# pokey.net
KiCad netlist of a schematic drawn in Altium Designer
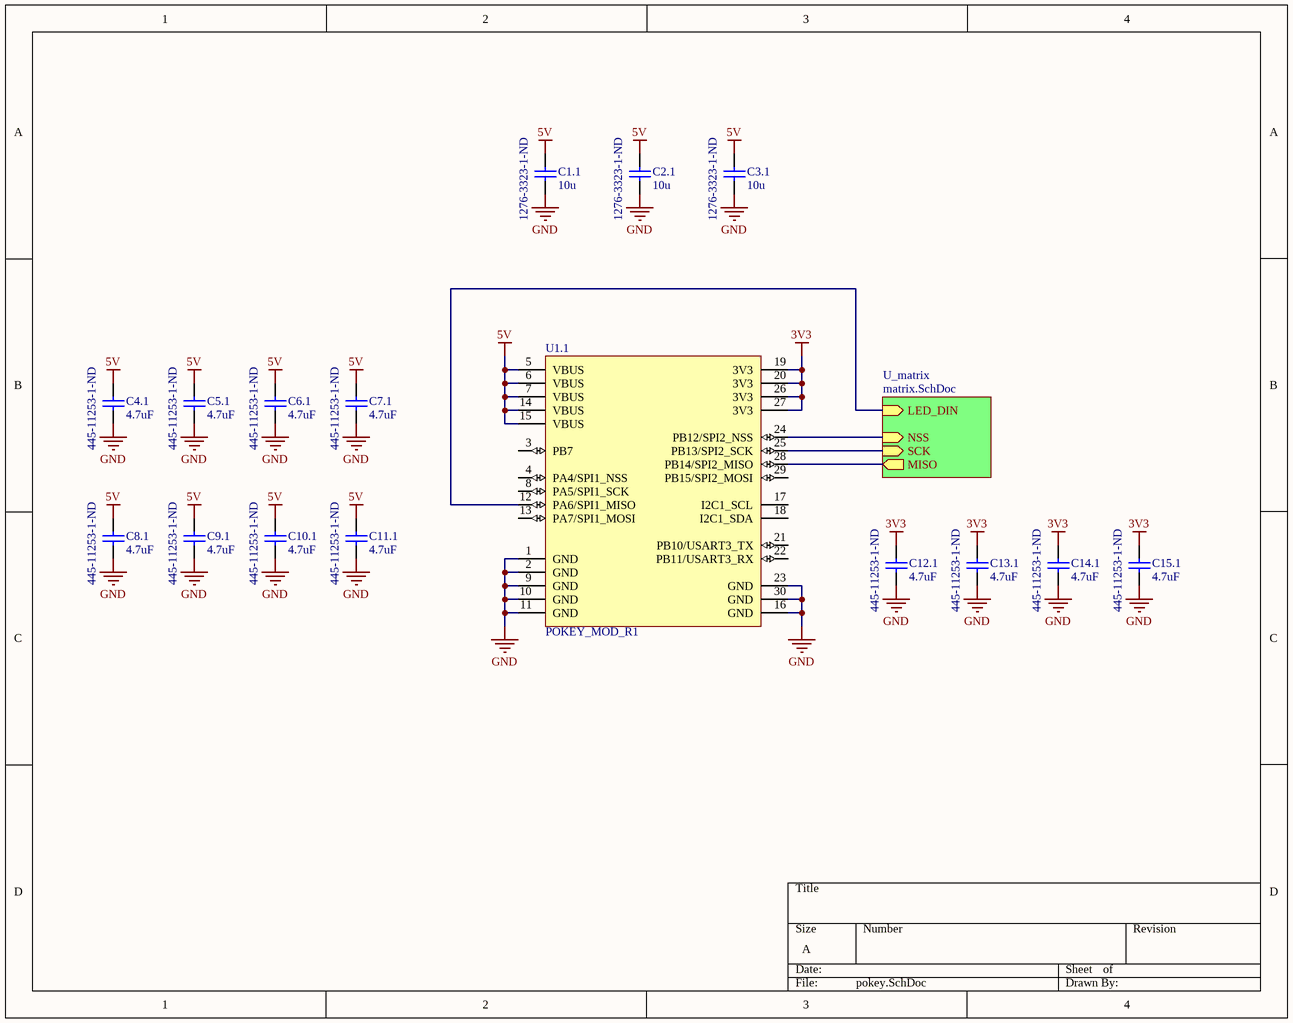
[diagram p0: pokey.SchDoc]

(export (version "E")
  (design (tool "Eeschema 10.0.6"))
  (components
    (comp (ref "C1.1")
      (value "10u")
      (footprint "1210")
      (fields
        (field (name "SUPPLIER PART NUMBER 1") "1276-3323-1-ND")
        (field (name "TOLERANCE") "10%")
        (field (name "VOLTAGE") "35V")
      )
      (libsource (lib "Luminaire") (part "CAPACITOR NON_POL"))
    )
    (comp (ref "C2.1")
      (value "10u")
      (footprint "1210")
      (fields
        (field (name "SUPPLIER PART NUMBER 1") "1276-3323-1-ND")
        (field (name "TOLERANCE") "10%")
        (field (name "VOLTAGE") "35V")
      )
      (libsource (lib "Luminaire") (part "CAPACITOR NON_POL"))
    )
    (comp (ref "C3.1")
      (value "10u")
      (footprint "1210")
      (fields
        (field (name "SUPPLIER PART NUMBER 1") "1276-3323-1-ND")
        (field (name "TOLERANCE") "10%")
        (field (name "VOLTAGE") "35V")
      )
      (libsource (lib "Luminaire") (part "CAPACITOR NON_POL"))
    )
    (comp (ref "C4.1")
      (value "4.7uF")
      (footprint "1608[0603]")
      (fields (field (name "SUPPLIER PART NUMBER 1") "445-11253-1-ND"))
      (libsource (lib "KEMET Chip Capacitor") (part "C0402"))
    )
    (comp (ref "C5.1")
      (value "4.7uF")
      (footprint "1608[0603]")
      (fields (field (name "SUPPLIER PART NUMBER 1") "445-11253-1-ND"))
      (libsource (lib "KEMET Chip Capacitor") (part "C0402"))
    )
    (comp (ref "C6.1")
      (value "4.7uF")
      (footprint "1608[0603]")
      (fields (field (name "SUPPLIER PART NUMBER 1") "445-11253-1-ND"))
      (libsource (lib "KEMET Chip Capacitor") (part "C0402"))
    )
    (comp (ref "C7.1")
      (value "4.7uF")
      (footprint "1608[0603]")
      (fields (field (name "SUPPLIER PART NUMBER 1") "445-11253-1-ND"))
      (libsource (lib "KEMET Chip Capacitor") (part "C0402"))
    )
    (comp (ref "C8.1")
      (value "4.7uF")
      (footprint "1608[0603]")
      (fields (field (name "SUPPLIER PART NUMBER 1") "445-11253-1-ND"))
      (libsource (lib "KEMET Chip Capacitor") (part "C0402"))
    )
    (comp (ref "C9.1")
      (value "4.7uF")
      (footprint "1608[0603]")
      (fields (field (name "SUPPLIER PART NUMBER 1") "445-11253-1-ND"))
      (libsource (lib "KEMET Chip Capacitor") (part "C0402"))
    )
    (comp (ref "C10.1")
      (value "4.7uF")
      (footprint "1608[0603]")
      (fields (field (name "SUPPLIER PART NUMBER 1") "445-11253-1-ND"))
      (libsource (lib "KEMET Chip Capacitor") (part "C0402"))
    )
    (comp (ref "C11.1")
      (value "4.7uF")
      (footprint "1608[0603]")
      (fields (field (name "SUPPLIER PART NUMBER 1") "445-11253-1-ND"))
      (libsource (lib "KEMET Chip Capacitor") (part "C0402"))
    )
    (comp (ref "C12.1")
      (value "4.7uF")
      (footprint "1608[0603]")
      (fields (field (name "SUPPLIER PART NUMBER 1") "445-11253-1-ND"))
      (libsource (lib "KEMET Chip Capacitor") (part "C0402"))
    )
    (comp (ref "C13.1")
      (value "4.7uF")
      (footprint "1608[0603]")
      (fields (field (name "SUPPLIER PART NUMBER 1") "445-11253-1-ND"))
      (libsource (lib "KEMET Chip Capacitor") (part "C0402"))
    )
    (comp (ref "C14.1")
      (value "4.7uF")
      (footprint "1608[0603]")
      (fields (field (name "SUPPLIER PART NUMBER 1") "445-11253-1-ND"))
      (libsource (lib "KEMET Chip Capacitor") (part "C0402"))
    )
    (comp (ref "C15.1")
      (value "4.7uF")
      (footprint "1608[0603]")
      (fields (field (name "SUPPLIER PART NUMBER 1") "445-11253-1-ND"))
      (libsource (lib "KEMET Chip Capacitor") (part "C0402"))
    )
    (comp (ref "U1.1")
      (value "POKEY_MOD_R1")
      (footprint "POKEY_MOD_R1")
      (libsource (lib "pokey") (part "POKEY_MOD_R1"))
    )
  )
  (nets
    (net (code "1") (name "/LED_DIN") (class "Default")
      (node (ref "U1.1") (pin "12") (pinfunction "PA6/SPI1_MISO_12") (pintype "bidirectional"))
    )
    (net (code "2") (name "/MISO") (class "Default")
      (node (ref "U1.1") (pin "28") (pinfunction "PB14/SPI2_MISO_28") (pintype "bidirectional"))
    )
    (net (code "3") (name "/NSS") (class "Default")
      (node (ref "U1.1") (pin "24") (pinfunction "PB12/SPI2_NSS_24") (pintype "bidirectional"))
    )
    (net (code "4") (name "/SCK") (class "Default")
      (node (ref "U1.1") (pin "25") (pinfunction "PB13/SPI2_SCK_25") (pintype "bidirectional"))
    )
    (net (code "5") (name "3V3") (class "Default")
      (node (ref "C12.1") (pin "2") (pinfunction "2_2") (pintype "passive"))
      (node (ref "C13.1") (pin "2") (pinfunction "2_2") (pintype "passive"))
      (node (ref "C14.1") (pin "2") (pinfunction "2_2") (pintype "passive"))
      (node (ref "C15.1") (pin "2") (pinfunction "2_2") (pintype "passive"))
      (node (ref "U1.1") (pin "19") (pinfunction "3V3_19") (pintype "power_in"))
      (node (ref "U1.1") (pin "20") (pinfunction "3V3_20") (pintype "power_in"))
      (node (ref "U1.1") (pin "26") (pinfunction "3V3_26") (pintype "power_in"))
      (node (ref "U1.1") (pin "27") (pinfunction "3V3_27") (pintype "power_in"))
    )
    (net (code "6") (name "5V") (class "Default")
      (node (ref "C1.1") (pin "2") (pinfunction "2_2") (pintype "passive"))
      (node (ref "C10.1") (pin "2") (pinfunction "2_2") (pintype "passive"))
      (node (ref "C11.1") (pin "2") (pinfunction "2_2") (pintype "passive"))
      (node (ref "C2.1") (pin "2") (pinfunction "2_2") (pintype "passive"))
      (node (ref "C3.1") (pin "2") (pinfunction "2_2") (pintype "passive"))
      (node (ref "C4.1") (pin "2") (pinfunction "2_2") (pintype "passive"))
      (node (ref "C5.1") (pin "2") (pinfunction "2_2") (pintype "passive"))
      (node (ref "C6.1") (pin "2") (pinfunction "2_2") (pintype "passive"))
      (node (ref "C7.1") (pin "2") (pinfunction "2_2") (pintype "passive"))
      (node (ref "C8.1") (pin "2") (pinfunction "2_2") (pintype "passive"))
      (node (ref "C9.1") (pin "2") (pinfunction "2_2") (pintype "passive"))
      (node (ref "U1.1") (pin "14") (pinfunction "VBUS_14") (pintype "power_in"))
      (node (ref "U1.1") (pin "15") (pinfunction "VBUS_15") (pintype "power_in"))
      (node (ref "U1.1") (pin "5") (pinfunction "VBUS_5") (pintype "power_in"))
      (node (ref "U1.1") (pin "6") (pinfunction "VBUS_6") (pintype "power_in"))
      (node (ref "U1.1") (pin "7") (pinfunction "VBUS_7") (pintype "power_in"))
    )
    (net (code "7") (name "GND") (class "Default")
      (node (ref "C1.1") (pin "1") (pinfunction "1_1") (pintype "passive"))
      (node (ref "C10.1") (pin "1") (pinfunction "1_1") (pintype "passive"))
      (node (ref "C11.1") (pin "1") (pinfunction "1_1") (pintype "passive"))
      (node (ref "C12.1") (pin "1") (pinfunction "1_1") (pintype "passive"))
      (node (ref "C13.1") (pin "1") (pinfunction "1_1") (pintype "passive"))
      (node (ref "C14.1") (pin "1") (pinfunction "1_1") (pintype "passive"))
      (node (ref "C15.1") (pin "1") (pinfunction "1_1") (pintype "passive"))
      (node (ref "C2.1") (pin "1") (pinfunction "1_1") (pintype "passive"))
      (node (ref "C3.1") (pin "1") (pinfunction "1_1") (pintype "passive"))
      (node (ref "C4.1") (pin "1") (pinfunction "1_1") (pintype "passive"))
      (node (ref "C5.1") (pin "1") (pinfunction "1_1") (pintype "passive"))
      (node (ref "C6.1") (pin "1") (pinfunction "1_1") (pintype "passive"))
      (node (ref "C7.1") (pin "1") (pinfunction "1_1") (pintype "passive"))
      (node (ref "C8.1") (pin "1") (pinfunction "1_1") (pintype "passive"))
      (node (ref "C9.1") (pin "1") (pinfunction "1_1") (pintype "passive"))
      (node (ref "U1.1") (pin "1") (pinfunction "GND_1") (pintype "power_in"))
      (node (ref "U1.1") (pin "10") (pinfunction "GND_10") (pintype "power_in"))
      (node (ref "U1.1") (pin "11") (pinfunction "GND_11") (pintype "power_in"))
      (node (ref "U1.1") (pin "16") (pinfunction "GND_16") (pintype "power_in"))
      (node (ref "U1.1") (pin "2") (pinfunction "GND_2") (pintype "power_in"))
      (node (ref "U1.1") (pin "23") (pinfunction "GND_23") (pintype "power_in"))
      (node (ref "U1.1") (pin "30") (pinfunction "GND_30") (pintype "power_in"))
      (node (ref "U1.1") (pin "9") (pinfunction "GND_9") (pintype "power_in"))
    )
    (net (code "8") (name "unconnected-(U1.1-I2C1_SCL-Pad17)") (class "Default")
      (node (ref "U1.1") (pin "17") (pinfunction "I2C1_SCL_17") (pintype "open_collector"))
    )
    (net (code "9") (name "unconnected-(U1.1-I2C1_SDA-Pad18)") (class "Default")
      (node (ref "U1.1") (pin "18") (pinfunction "I2C1_SDA_18") (pintype "open_collector"))
    )
    (net (code "10") (name "unconnected-(U1.1-PA4{slash}SPI1_NSS-Pad4)") (class "Default")
      (node (ref "U1.1") (pin "4") (pinfunction "PA4/SPI1_NSS_4") (pintype "bidirectional"))
    )
    (net (code "11") (name "unconnected-(U1.1-PA5{slash}SPI1_SCK-Pad8)") (class "Default")
      (node (ref "U1.1") (pin "8") (pinfunction "PA5/SPI1_SCK_8") (pintype "bidirectional"))
    )
    (net (code "12") (name "unconnected-(U1.1-PA7{slash}SPI1_MOSI-Pad13)") (class "Default")
      (node (ref "U1.1") (pin "13") (pinfunction "PA7/SPI1_MOSI_13") (pintype "bidirectional"))
    )
    (net (code "13") (name "unconnected-(U1.1-PB7-Pad3)") (class "Default")
      (node (ref "U1.1") (pin "3") (pinfunction "PB7_3") (pintype "bidirectional"))
    )
    (net (code "14") (name "unconnected-(U1.1-PB10{slash}USART3_TX-Pad21)") (class "Default")
      (node (ref "U1.1") (pin "21") (pinfunction "PB10/USART3_TX_21") (pintype "bidirectional"))
    )
    (net (code "15") (name "unconnected-(U1.1-PB11{slash}USART3_RX-Pad22)") (class "Default")
      (node (ref "U1.1") (pin "22") (pinfunction "PB11/USART3_RX_22") (pintype "bidirectional"))
    )
    (net (code "16") (name "unconnected-(U1.1-PB15{slash}SPI2_MOSI-Pad29)") (class "Default")
      (node (ref "U1.1") (pin "29") (pinfunction "PB15/SPI2_MOSI_29") (pintype "bidirectional"))
    )
  )
)
